# Radio_and_GPS_Rev_A.net
KiCad netlist of a schematic drawn in EAGLE
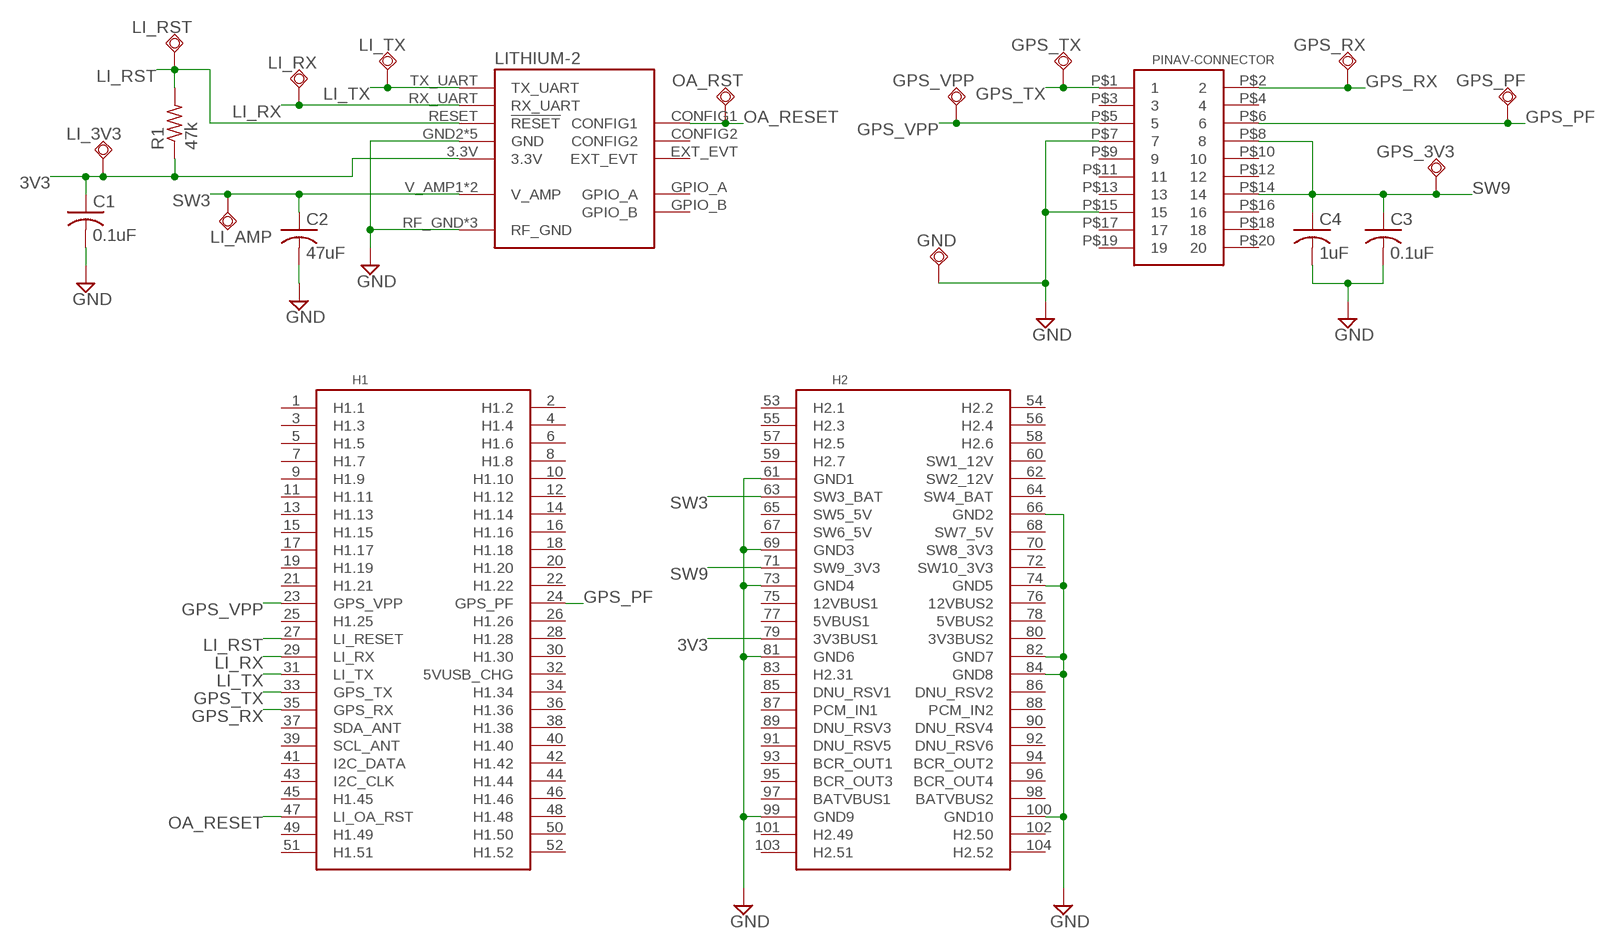
[diagram p0: schematic, sheet 1]

(export (version "E")
  (design (tool "Eeschema 10.0.6"))
  (components
    (comp (ref "C1")
      (value "0.1uF")
      (footprint "eagle-import:C0805")
      (libsource (lib "eagle-import") (part "C-USC0805"))
    )
    (comp (ref "C2")
      (value "47uF")
      (footprint "eagle-import:C0805")
      (libsource (lib "eagle-import") (part "C-USC0805"))
    )
    (comp (ref "C3")
      (value "0.1uF")
      (footprint "eagle-import:C0805")
      (libsource (lib "eagle-import") (part "C-USC0805"))
    )
    (comp (ref "C4")
      (value "1uF")
      (footprint "eagle-import:C0805")
      (libsource (lib "eagle-import") (part "C-USC0805"))
    )
    (comp (ref "GND")
      (value "TPSQTP10SQ")
      (footprint "eagle-import:TP10SQ")
      (libsource (lib "eagle-import") (part "TPSQTP10SQ"))
    )
    (comp (ref "GPS_3V3")
      (value "TPSQTP10SQ")
      (footprint "eagle-import:TP10SQ")
      (libsource (lib "eagle-import") (part "TPSQTP10SQ"))
    )
    (comp (ref "GPS_PF")
      (value "TPSQTP10SQ")
      (footprint "eagle-import:TP10SQ")
      (libsource (lib "eagle-import") (part "TPSQTP10SQ"))
    )
    (comp (ref "GPS_RX")
      (value "TPSQTP10SQ")
      (footprint "eagle-import:TP10SQ")
      (libsource (lib "eagle-import") (part "TPSQTP10SQ"))
    )
    (comp (ref "GPS_TX")
      (value "TPSQTP10SQ")
      (footprint "eagle-import:TP10SQ")
      (libsource (lib "eagle-import") (part "TPSQTP10SQ"))
    )
    (comp (ref "GPS_VPP")
      (value "TPSQTP10SQ")
      (footprint "eagle-import:TP10SQ")
      (libsource (lib "eagle-import") (part "TPSQTP10SQ"))
    )
    (comp (ref "LITHIUM-2")
      (value "LI-2")
      (footprint "eagle-import:LI-2")
      (libsource (lib "eagle-import") (part "LI-2"))
    )
    (comp (ref "LI_3V3")
      (value "TPSQTP10SQ")
      (footprint "eagle-import:TP10SQ")
      (libsource (lib "eagle-import") (part "TPSQTP10SQ"))
    )
    (comp (ref "LI_AMP")
      (value "TPSQTP10SQ")
      (footprint "eagle-import:TP10SQ")
      (libsource (lib "eagle-import") (part "TPSQTP10SQ"))
    )
    (comp (ref "LI_RST")
      (value "TPSQTP10SQ")
      (footprint "eagle-import:TP10SQ")
      (libsource (lib "eagle-import") (part "TPSQTP10SQ"))
    )
    (comp (ref "LI_RX")
      (value "TPSQTP10SQ")
      (footprint "eagle-import:TP10SQ")
      (libsource (lib "eagle-import") (part "TPSQTP10SQ"))
    )
    (comp (ref "LI_TX")
      (value "TPSQTP10SQ")
      (footprint "eagle-import:TP10SQ")
      (libsource (lib "eagle-import") (part "TPSQTP10SQ"))
    )
    (comp (ref "OA_RST")
      (value "TPSQTP10SQ")
      (footprint "eagle-import:TP10SQ")
      (libsource (lib "eagle-import") (part "TPSQTP10SQ"))
    )
    (comp (ref "PINAV-CONNECTOR")
      (value "HLE-110-02-X-DVHLE-110-X-DV-PE-BA")
      (footprint "eagle-import:HLE-110-02-X-DV-PE-BE")
      (libsource (lib "eagle-import") (part "HLE-110-02-X-DVHLE-110-X-DV-PE-BA"))
    )
    (comp (ref "R1")
      (value "47k")
      (footprint "eagle-import:R0805")
      (libsource (lib "eagle-import") (part "R-US_R0805"))
    )
    (comp (ref "U$1")
      (value "PC104_NO_DIMENSION")
      (footprint "eagle-import:PC104_NO_DIMENSION")
      (libsource (lib "eagle-import") (part "PC104_NO_DIMENSION"))
    )
  )
  (nets
    (net (code "1") (name "/3V3") (class "Default")
      (node (ref "C1") (pin "1") (pinfunction "1_1") (pintype "passive"))
      (node (ref "LITHIUM-2") (pin "3.3V") (pinfunction "3.3V_3.3V") (pintype "power_in"))
      (node (ref "LI_3V3") (pin "TP") (pinfunction "TP_TP") (pintype "input"))
      (node (ref "R1") (pin "1") (pinfunction "1_1") (pintype "passive"))
      (node (ref "U$1") (pin "79") (pinfunction "3V3BUS1_79") (pintype "bidirectional"))
    )
    (net (code "2") (name "/GPS_PF") (class "Default")
      (node (ref "GPS_PF") (pin "TP") (pinfunction "TP_TP") (pintype "input"))
      (node (ref "PINAV-CONNECTOR") (pin "P$6") (pinfunction "6_P$6") (pintype "bidirectional"))
      (node (ref "U$1") (pin "24") (pinfunction "GPS_PF_24") (pintype "bidirectional"))
    )
    (net (code "3") (name "/GPS_RX") (class "Default")
      (node (ref "GPS_RX") (pin "TP") (pinfunction "TP_TP") (pintype "input"))
      (node (ref "PINAV-CONNECTOR") (pin "P$2") (pinfunction "2_P$2") (pintype "bidirectional"))
      (node (ref "U$1") (pin "35") (pinfunction "GPS_RX_35") (pintype "bidirectional"))
    )
    (net (code "4") (name "/GPS_TX") (class "Default")
      (node (ref "GPS_TX") (pin "TP") (pinfunction "TP_TP") (pintype "input"))
      (node (ref "PINAV-CONNECTOR") (pin "P$1") (pinfunction "1_P$1") (pintype "bidirectional"))
      (node (ref "U$1") (pin "33") (pinfunction "GPS_TX_33") (pintype "bidirectional"))
    )
    (net (code "5") (name "/GPS_VPP") (class "Default")
      (node (ref "GPS_VPP") (pin "TP") (pinfunction "TP_TP") (pintype "input"))
      (node (ref "PINAV-CONNECTOR") (pin "P$5") (pinfunction "5_P$5") (pintype "bidirectional"))
      (node (ref "U$1") (pin "23") (pinfunction "GPS_VPP_23") (pintype "bidirectional"))
    )
    (net (code "6") (name "/LI_RST") (class "Default")
      (node (ref "LITHIUM-2") (pin "RESET") (pinfunction "~{RESET}_RESET") (pintype "input"))
      (node (ref "LI_RST") (pin "TP") (pinfunction "TP_TP") (pintype "input"))
      (node (ref "R1") (pin "2") (pinfunction "2_2") (pintype "passive"))
      (node (ref "U$1") (pin "27") (pinfunction "LI_RESET_27") (pintype "bidirectional"))
    )
    (net (code "7") (name "/LI_RX") (class "Default")
      (node (ref "LITHIUM-2") (pin "RX_UART") (pinfunction "RX_UART_RX_UART") (pintype "input"))
      (node (ref "LI_RX") (pin "TP") (pinfunction "TP_TP") (pintype "input"))
      (node (ref "U$1") (pin "29") (pinfunction "LI_RX_29") (pintype "bidirectional"))
    )
    (net (code "8") (name "/LI_TX") (class "Default")
      (node (ref "LITHIUM-2") (pin "TX_UART") (pinfunction "TX_UART_TX_UART") (pintype "output"))
      (node (ref "LI_TX") (pin "TP") (pinfunction "TP_TP") (pintype "input"))
      (node (ref "U$1") (pin "31") (pinfunction "LI_TX_31") (pintype "bidirectional"))
    )
    (net (code "9") (name "/OA_RESET") (class "Default")
      (node (ref "LITHIUM-2") (pin "CONFIG1") (pinfunction "CONFIG1_CONFIG1") (pintype "bidirectional"))
      (node (ref "OA_RST") (pin "TP") (pinfunction "TP_TP") (pintype "input"))
      (node (ref "U$1") (pin "47") (pinfunction "LI_OA_RST_47") (pintype "bidirectional"))
    )
    (net (code "10") (name "/SW3") (class "Default")
      (node (ref "C2") (pin "1") (pinfunction "1_1") (pintype "passive"))
      (node (ref "LITHIUM-2") (pin "V_AMP1") (pinfunction "V_AMP_V_AMP1") (pintype "power_in"))
      (node (ref "LITHIUM-2") (pin "V_AMP2") (pinfunction "V_AMP_V_AMP2") (pintype "power_in"))
      (node (ref "LI_AMP") (pin "TP") (pinfunction "TP_TP") (pintype "input"))
      (node (ref "U$1") (pin "63") (pinfunction "SW3_BAT_63") (pintype "bidirectional"))
    )
    (net (code "11") (name "/SW9") (class "Default")
      (node (ref "C3") (pin "1") (pinfunction "1_1") (pintype "passive"))
      (node (ref "C4") (pin "1") (pinfunction "1_1") (pintype "passive"))
      (node (ref "GPS_3V3") (pin "TP") (pinfunction "TP_TP") (pintype "input"))
      (node (ref "PINAV-CONNECTOR") (pin "P$14") (pinfunction "14_P$14") (pintype "bidirectional"))
      (node (ref "PINAV-CONNECTOR") (pin "P$8") (pinfunction "8_P$8") (pintype "bidirectional"))
      (node (ref "U$1") (pin "71") (pinfunction "SW9_3V3_71") (pintype "bidirectional"))
    )
    (net (code "12") (name "GND") (class "Default")
      (node (ref "C1") (pin "2") (pinfunction "2_2") (pintype "passive"))
      (node (ref "C2") (pin "2") (pinfunction "2_2") (pintype "passive"))
      (node (ref "C3") (pin "2") (pinfunction "2_2") (pintype "passive"))
      (node (ref "C4") (pin "2") (pinfunction "2_2") (pintype "passive"))
      (node (ref "GND") (pin "TP") (pinfunction "TP_TP") (pintype "input"))
      (node (ref "LITHIUM-2") (pin "GND2") (pinfunction "GND_GND2") (pintype "power_in"))
      (node (ref "LITHIUM-2") (pin "RF_GND") (pinfunction "RF_GND_RF_GND") (pintype "power_in"))
      (node (ref "LITHIUM-2") (pin "RF_GND1") (pinfunction "RF_GND_RF_GND1") (pintype "power_in"))
      (node (ref "LITHIUM-2") (pin "RF_GND2") (pinfunction "RF_GND_RF_GND2") (pintype "power_in"))
      (node (ref "LITHIUM-2") (pin "THERM1") (pinfunction "GND_THERM1") (pintype "power_in"))
      (node (ref "LITHIUM-2") (pin "THERM2") (pinfunction "GND_THERM2") (pintype "power_in"))
      (node (ref "LITHIUM-2") (pin "THERM3") (pinfunction "GND_THERM3") (pintype "power_in"))
      (node (ref "LITHIUM-2") (pin "THERM4") (pinfunction "GND_THERM4") (pintype "power_in"))
      (node (ref "PINAV-CONNECTOR") (pin "P$15") (pinfunction "15_P$15") (pintype "bidirectional"))
      (node (ref "PINAV-CONNECTOR") (pin "P$7") (pinfunction "7_P$7") (pintype "bidirectional"))
      (node (ref "U$1") (pin "100") (pinfunction "GND10_100") (pintype "bidirectional"))
      (node (ref "U$1") (pin "61") (pinfunction "GND1_61") (pintype "bidirectional"))
      (node (ref "U$1") (pin "66") (pinfunction "GND2_66") (pintype "bidirectional"))
      (node (ref "U$1") (pin "69") (pinfunction "GND3_69") (pintype "bidirectional"))
      (node (ref "U$1") (pin "73") (pinfunction "GND4_73") (pintype "bidirectional"))
      (node (ref "U$1") (pin "74") (pinfunction "GND5_74") (pintype "bidirectional"))
      (node (ref "U$1") (pin "81") (pinfunction "GND6_81") (pintype "bidirectional"))
      (node (ref "U$1") (pin "82") (pinfunction "GND7_82") (pintype "bidirectional"))
      (node (ref "U$1") (pin "84") (pinfunction "GND8_84") (pintype "bidirectional"))
      (node (ref "U$1") (pin "99") (pinfunction "GND9_99") (pintype "bidirectional"))
    )
    (net (code "13") (name "unconnected-(LITHIUM-2-PadCONFIG2)") (class "Default")
      (node (ref "LITHIUM-2") (pin "CONFIG2") (pinfunction "CONFIG2_CONFIG2") (pintype "bidirectional"))
    )
    (net (code "14") (name "unconnected-(LITHIUM-2-PadEXT_EVT)") (class "Default")
      (node (ref "LITHIUM-2") (pin "EXT_EVT") (pinfunction "EXT_EVT_EXT_EVT") (pintype "bidirectional"))
    )
    (net (code "15") (name "unconnected-(LITHIUM-2-PadGPIO_A)") (class "Default")
      (node (ref "LITHIUM-2") (pin "GPIO_A") (pinfunction "GPIO_A_GPIO_A") (pintype "bidirectional"))
    )
    (net (code "16") (name "unconnected-(LITHIUM-2-PadGPIO_B)") (class "Default")
      (node (ref "LITHIUM-2") (pin "GPIO_B") (pinfunction "GPIO_B_GPIO_B") (pintype "bidirectional"))
    )
    (net (code "17") (name "unconnected-(PINAV-CONNECTOR-3-PadP$3)") (class "Default")
      (node (ref "PINAV-CONNECTOR") (pin "P$3") (pinfunction "3_P$3") (pintype "bidirectional"))
    )
    (net (code "18") (name "unconnected-(PINAV-CONNECTOR-4-PadP$4)") (class "Default")
      (node (ref "PINAV-CONNECTOR") (pin "P$4") (pinfunction "4_P$4") (pintype "bidirectional"))
    )
    (net (code "19") (name "unconnected-(PINAV-CONNECTOR-9-PadP$9)") (class "Default")
      (node (ref "PINAV-CONNECTOR") (pin "P$9") (pinfunction "9_P$9") (pintype "bidirectional"))
    )
    (net (code "20") (name "unconnected-(PINAV-CONNECTOR-10-PadP$10)") (class "Default")
      (node (ref "PINAV-CONNECTOR") (pin "P$10") (pinfunction "10_P$10") (pintype "bidirectional"))
    )
    (net (code "21") (name "unconnected-(PINAV-CONNECTOR-11-PadP$11)") (class "Default")
      (node (ref "PINAV-CONNECTOR") (pin "P$11") (pinfunction "11_P$11") (pintype "bidirectional"))
    )
    (net (code "22") (name "unconnected-(PINAV-CONNECTOR-12-PadP$12)") (class "Default")
      (node (ref "PINAV-CONNECTOR") (pin "P$12") (pinfunction "12_P$12") (pintype "bidirectional"))
    )
    (net (code "23") (name "unconnected-(PINAV-CONNECTOR-13-PadP$13)") (class "Default")
      (node (ref "PINAV-CONNECTOR") (pin "P$13") (pinfunction "13_P$13") (pintype "bidirectional"))
    )
    (net (code "24") (name "unconnected-(PINAV-CONNECTOR-16-PadP$16)") (class "Default")
      (node (ref "PINAV-CONNECTOR") (pin "P$16") (pinfunction "16_P$16") (pintype "bidirectional"))
    )
    (net (code "25") (name "unconnected-(PINAV-CONNECTOR-17-PadP$17)") (class "Default")
      (node (ref "PINAV-CONNECTOR") (pin "P$17") (pinfunction "17_P$17") (pintype "bidirectional"))
    )
    (net (code "26") (name "unconnected-(PINAV-CONNECTOR-18-PadP$18)") (class "Default")
      (node (ref "PINAV-CONNECTOR") (pin "P$18") (pinfunction "18_P$18") (pintype "bidirectional"))
    )
    (net (code "27") (name "unconnected-(PINAV-CONNECTOR-19-PadP$19)") (class "Default")
      (node (ref "PINAV-CONNECTOR") (pin "P$19") (pinfunction "19_P$19") (pintype "bidirectional"))
    )
    (net (code "28") (name "unconnected-(PINAV-CONNECTOR-20-PadP$20)") (class "Default")
      (node (ref "PINAV-CONNECTOR") (pin "P$20") (pinfunction "20_P$20") (pintype "bidirectional"))
    )
    (net (code "29") (name "unconnected-(U$1-3V3BUS2-Pad80)") (class "Default")
      (node (ref "U$1") (pin "80") (pinfunction "3V3BUS2_80") (pintype "bidirectional"))
    )
    (net (code "30") (name "unconnected-(U$1-5VBUS1-Pad77)") (class "Default")
      (node (ref "U$1") (pin "77") (pinfunction "5VBUS1_77") (pintype "bidirectional"))
    )
    (net (code "31") (name "unconnected-(U$1-5VBUS2-Pad78)") (class "Default")
      (node (ref "U$1") (pin "78") (pinfunction "5VBUS2_78") (pintype "bidirectional"))
    )
    (net (code "32") (name "unconnected-(U$1-5VUSB_CHG-Pad32)") (class "Default")
      (node (ref "U$1") (pin "32") (pinfunction "5VUSB_CHG_32") (pintype "bidirectional"))
    )
    (net (code "33") (name "unconnected-(U$1-12VBUS1-Pad75)") (class "Default")
      (node (ref "U$1") (pin "75") (pinfunction "12VBUS1_75") (pintype "bidirectional"))
    )
    (net (code "34") (name "unconnected-(U$1-12VBUS2-Pad76)") (class "Default")
      (node (ref "U$1") (pin "76") (pinfunction "12VBUS2_76") (pintype "bidirectional"))
    )
    (net (code "35") (name "unconnected-(U$1-BATVBUS1-Pad97)") (class "Default")
      (node (ref "U$1") (pin "97") (pinfunction "BATVBUS1_97") (pintype "bidirectional"))
    )
    (net (code "36") (name "unconnected-(U$1-BATVBUS2-Pad98)") (class "Default")
      (node (ref "U$1") (pin "98") (pinfunction "BATVBUS2_98") (pintype "bidirectional"))
    )
    (net (code "37") (name "unconnected-(U$1-BCR_OUT1-Pad93)") (class "Default")
      (node (ref "U$1") (pin "93") (pinfunction "BCR_OUT1_93") (pintype "bidirectional"))
    )
    (net (code "38") (name "unconnected-(U$1-BCR_OUT2-Pad94)") (class "Default")
      (node (ref "U$1") (pin "94") (pinfunction "BCR_OUT2_94") (pintype "bidirectional"))
    )
    (net (code "39") (name "unconnected-(U$1-BCR_OUT3-Pad95)") (class "Default")
      (node (ref "U$1") (pin "95") (pinfunction "BCR_OUT3_95") (pintype "bidirectional"))
    )
    (net (code "40") (name "unconnected-(U$1-BCR_OUT4-Pad96)") (class "Default")
      (node (ref "U$1") (pin "96") (pinfunction "BCR_OUT4_96") (pintype "bidirectional"))
    )
    (net (code "41") (name "unconnected-(U$1-DNU_RSV1-Pad85)") (class "Default")
      (node (ref "U$1") (pin "85") (pinfunction "DNU_RSV1_85") (pintype "bidirectional"))
    )
    (net (code "42") (name "unconnected-(U$1-DNU_RSV2-Pad86)") (class "Default")
      (node (ref "U$1") (pin "86") (pinfunction "DNU_RSV2_86") (pintype "bidirectional"))
    )
    (net (code "43") (name "unconnected-(U$1-DNU_RSV3-Pad89)") (class "Default")
      (node (ref "U$1") (pin "89") (pinfunction "DNU_RSV3_89") (pintype "bidirectional"))
    )
    (net (code "44") (name "unconnected-(U$1-DNU_RSV4-Pad90)") (class "Default")
      (node (ref "U$1") (pin "90") (pinfunction "DNU_RSV4_90") (pintype "bidirectional"))
    )
    (net (code "45") (name "unconnected-(U$1-DNU_RSV5-Pad91)") (class "Default")
      (node (ref "U$1") (pin "91") (pinfunction "DNU_RSV5_91") (pintype "bidirectional"))
    )
    (net (code "46") (name "unconnected-(U$1-DNU_RSV6-Pad92)") (class "Default")
      (node (ref "U$1") (pin "92") (pinfunction "DNU_RSV6_92") (pintype "bidirectional"))
    )
    (net (code "47") (name "unconnected-(U$1-H1.1-Pad1)") (class "Default")
      (node (ref "U$1") (pin "1") (pinfunction "H1.1_1") (pintype "bidirectional"))
    )
    (net (code "48") (name "unconnected-(U$1-H1.2-Pad2)") (class "Default")
      (node (ref "U$1") (pin "2") (pinfunction "H1.2_2") (pintype "bidirectional"))
    )
    (net (code "49") (name "unconnected-(U$1-H1.3-Pad3)") (class "Default")
      (node (ref "U$1") (pin "3") (pinfunction "H1.3_3") (pintype "bidirectional"))
    )
    (net (code "50") (name "unconnected-(U$1-H1.4-Pad4)") (class "Default")
      (node (ref "U$1") (pin "4") (pinfunction "H1.4_4") (pintype "bidirectional"))
    )
    (net (code "51") (name "unconnected-(U$1-H1.5-Pad5)") (class "Default")
      (node (ref "U$1") (pin "5") (pinfunction "H1.5_5") (pintype "bidirectional"))
    )
    (net (code "52") (name "unconnected-(U$1-H1.6-Pad6)") (class "Default")
      (node (ref "U$1") (pin "6") (pinfunction "H1.6_6") (pintype "bidirectional"))
    )
    (net (code "53") (name "unconnected-(U$1-H1.7-Pad7)") (class "Default")
      (node (ref "U$1") (pin "7") (pinfunction "H1.7_7") (pintype "bidirectional"))
    )
    (net (code "54") (name "unconnected-(U$1-H1.8-Pad8)") (class "Default")
      (node (ref "U$1") (pin "8") (pinfunction "H1.8_8") (pintype "bidirectional"))
    )
    (net (code "55") (name "unconnected-(U$1-H1.9-Pad9)") (class "Default")
      (node (ref "U$1") (pin "9") (pinfunction "H1.9_9") (pintype "bidirectional"))
    )
    (net (code "56") (name "unconnected-(U$1-H1.10-Pad10)") (class "Default")
      (node (ref "U$1") (pin "10") (pinfunction "H1.10_10") (pintype "bidirectional"))
    )
    (net (code "57") (name "unconnected-(U$1-H1.11-Pad11)") (class "Default")
      (node (ref "U$1") (pin "11") (pinfunction "H1.11_11") (pintype "bidirectional"))
    )
    (net (code "58") (name "unconnected-(U$1-H1.12-Pad12)") (class "Default")
      (node (ref "U$1") (pin "12") (pinfunction "H1.12_12") (pintype "bidirectional"))
    )
    (net (code "59") (name "unconnected-(U$1-H1.13-Pad13)") (class "Default")
      (node (ref "U$1") (pin "13") (pinfunction "H1.13_13") (pintype "bidirectional"))
    )
    (net (code "60") (name "unconnected-(U$1-H1.14-Pad14)") (class "Default")
      (node (ref "U$1") (pin "14") (pinfunction "H1.14_14") (pintype "bidirectional"))
    )
    (net (code "61") (name "unconnected-(U$1-H1.15-Pad15)") (class "Default")
      (node (ref "U$1") (pin "15") (pinfunction "H1.15_15") (pintype "bidirectional"))
    )
    (net (code "62") (name "unconnected-(U$1-H1.16-Pad16)") (class "Default")
      (node (ref "U$1") (pin "16") (pinfunction "H1.16_16") (pintype "bidirectional"))
    )
    (net (code "63") (name "unconnected-(U$1-H1.17-Pad17)") (class "Default")
      (node (ref "U$1") (pin "17") (pinfunction "H1.17_17") (pintype "bidirectional"))
    )
    (net (code "64") (name "unconnected-(U$1-H1.18-Pad18)") (class "Default")
      (node (ref "U$1") (pin "18") (pinfunction "H1.18_18") (pintype "bidirectional"))
    )
    (net (code "65") (name "unconnected-(U$1-H1.19-Pad19)") (class "Default")
      (node (ref "U$1") (pin "19") (pinfunction "H1.19_19") (pintype "bidirectional"))
    )
    (net (code "66") (name "unconnected-(U$1-H1.20-Pad20)") (class "Default")
      (node (ref "U$1") (pin "20") (pinfunction "H1.20_20") (pintype "bidirectional"))
    )
    (net (code "67") (name "unconnected-(U$1-H1.21-Pad21)") (class "Default")
      (node (ref "U$1") (pin "21") (pinfunction "H1.21_21") (pintype "bidirectional"))
    )
    (net (code "68") (name "unconnected-(U$1-H1.22-Pad22)") (class "Default")
      (node (ref "U$1") (pin "22") (pinfunction "H1.22_22") (pintype "bidirectional"))
    )
    (net (code "69") (name "unconnected-(U$1-H1.25-Pad25)") (class "Default")
      (node (ref "U$1") (pin "25") (pinfunction "H1.25_25") (pintype "bidirectional"))
    )
    (net (code "70") (name "unconnected-(U$1-H1.26-Pad26)") (class "Default")
      (node (ref "U$1") (pin "26") (pinfunction "H1.26_26") (pintype "bidirectional"))
    )
    (net (code "71") (name "unconnected-(U$1-H1.28-Pad28)") (class "Default")
      (node (ref "U$1") (pin "28") (pinfunction "H1.28_28") (pintype "bidirectional"))
    )
    (net (code "72") (name "unconnected-(U$1-H1.30-Pad30)") (class "Default")
      (node (ref "U$1") (pin "30") (pinfunction "H1.30_30") (pintype "bidirectional"))
    )
    (net (code "73") (name "unconnected-(U$1-H1.34-Pad34)") (class "Default")
      (node (ref "U$1") (pin "34") (pinfunction "H1.34_34") (pintype "bidirectional"))
    )
    (net (code "74") (name "unconnected-(U$1-H1.36-Pad36)") (class "Default")
      (node (ref "U$1") (pin "36") (pinfunction "H1.36_36") (pintype "bidirectional"))
    )
    (net (code "75") (name "unconnected-(U$1-H1.38-Pad38)") (class "Default")
      (node (ref "U$1") (pin "38") (pinfunction "H1.38_38") (pintype "bidirectional"))
    )
    (net (code "76") (name "unconnected-(U$1-H1.40-Pad40)") (class "Default")
      (node (ref "U$1") (pin "40") (pinfunction "H1.40_40") (pintype "bidirectional"))
    )
    (net (code "77") (name "unconnected-(U$1-H1.42-Pad42)") (class "Default")
      (node (ref "U$1") (pin "42") (pinfunction "H1.42_42") (pintype "bidirectional"))
    )
    (net (code "78") (name "unconnected-(U$1-H1.44-Pad44)") (class "Default")
      (node (ref "U$1") (pin "44") (pinfunction "H1.44_44") (pintype "bidirectional"))
    )
    (net (code "79") (name "unconnected-(U$1-H1.45-Pad45)") (class "Default")
      (node (ref "U$1") (pin "45") (pinfunction "H1.45_45") (pintype "bidirectional"))
    )
    (net (code "80") (name "unconnected-(U$1-H1.46-Pad46)") (class "Default")
      (node (ref "U$1") (pin "46") (pinfunction "H1.46_46") (pintype "bidirectional"))
    )
    (net (code "81") (name "unconnected-(U$1-H1.48-Pad48)") (class "Default")
      (node (ref "U$1") (pin "48") (pinfunction "H1.48_48") (pintype "bidirectional"))
    )
    (net (code "82") (name "unconnected-(U$1-H1.49-Pad49)") (class "Default")
      (node (ref "U$1") (pin "49") (pinfunction "H1.49_49") (pintype "bidirectional"))
    )
    (net (code "83") (name "unconnected-(U$1-H1.50-Pad50)") (class "Default")
      (node (ref "U$1") (pin "50") (pinfunction "H1.50_50") (pintype "bidirectional"))
    )
    (net (code "84") (name "unconnected-(U$1-H1.51-Pad51)") (class "Default")
      (node (ref "U$1") (pin "51") (pinfunction "H1.51_51") (pintype "bidirectional"))
    )
    (net (code "85") (name "unconnected-(U$1-H1.52-Pad52)") (class "Default")
      (node (ref "U$1") (pin "52") (pinfunction "H1.52_52") (pintype "bidirectional"))
    )
    (net (code "86") (name "unconnected-(U$1-H2.1-Pad53)") (class "Default")
      (node (ref "U$1") (pin "53") (pinfunction "H2.1_53") (pintype "bidirectional"))
    )
    (net (code "87") (name "unconnected-(U$1-H2.2-Pad54)") (class "Default")
      (node (ref "U$1") (pin "54") (pinfunction "H2.2_54") (pintype "bidirectional"))
    )
    (net (code "88") (name "unconnected-(U$1-H2.3-Pad55)") (class "Default")
      (node (ref "U$1") (pin "55") (pinfunction "H2.3_55") (pintype "bidirectional"))
    )
    (net (code "89") (name "unconnected-(U$1-H2.4-Pad56)") (class "Default")
      (node (ref "U$1") (pin "56") (pinfunction "H2.4_56") (pintype "bidirectional"))
    )
    (net (code "90") (name "unconnected-(U$1-H2.5-Pad57)") (class "Default")
      (node (ref "U$1") (pin "57") (pinfunction "H2.5_57") (pintype "bidirectional"))
    )
    (net (code "91") (name "unconnected-(U$1-H2.6-Pad58)") (class "Default")
      (node (ref "U$1") (pin "58") (pinfunction "H2.6_58") (pintype "bidirectional"))
    )
    (net (code "92") (name "unconnected-(U$1-H2.7-Pad59)") (class "Default")
      (node (ref "U$1") (pin "59") (pinfunction "H2.7_59") (pintype "bidirectional"))
    )
    (net (code "93") (name "unconnected-(U$1-H2.31-Pad83)") (class "Default")
      (node (ref "U$1") (pin "83") (pinfunction "H2.31_83") (pintype "bidirectional"))
    )
    (net (code "94") (name "unconnected-(U$1-H2.49-Pad101)") (class "Default")
      (node (ref "U$1") (pin "101") (pinfunction "H2.49_101") (pintype "bidirectional"))
    )
    (net (code "95") (name "unconnected-(U$1-H2.50-Pad102)") (class "Default")
      (node (ref "U$1") (pin "102") (pinfunction "H2.50_102") (pintype "bidirectional"))
    )
    (net (code "96") (name "unconnected-(U$1-H2.51-Pad103)") (class "Default")
      (node (ref "U$1") (pin "103") (pinfunction "H2.51_103") (pintype "bidirectional"))
    )
    (net (code "97") (name "unconnected-(U$1-H2.52-Pad104)") (class "Default")
      (node (ref "U$1") (pin "104") (pinfunction "H2.52_104") (pintype "bidirectional"))
    )
    (net (code "98") (name "unconnected-(U$1-I2C_CLK-Pad43)") (class "Default")
      (node (ref "U$1") (pin "43") (pinfunction "I2C_CLK_43") (pintype "bidirectional"))
    )
    (net (code "99") (name "unconnected-(U$1-I2C_DATA-Pad41)") (class "Default")
      (node (ref "U$1") (pin "41") (pinfunction "I2C_DATA_41") (pintype "bidirectional"))
    )
    (net (code "100") (name "unconnected-(U$1-PCM_IN1-Pad87)") (class "Default")
      (node (ref "U$1") (pin "87") (pinfunction "PCM_IN1_87") (pintype "bidirectional"))
    )
    (net (code "101") (name "unconnected-(U$1-PCM_IN2-Pad88)") (class "Default")
      (node (ref "U$1") (pin "88") (pinfunction "PCM_IN2_88") (pintype "bidirectional"))
    )
    (net (code "102") (name "unconnected-(U$1-SCL_ANT-Pad39)") (class "Default")
      (node (ref "U$1") (pin "39") (pinfunction "SCL_ANT_39") (pintype "bidirectional"))
    )
    (net (code "103") (name "unconnected-(U$1-SDA_ANT-Pad37)") (class "Default")
      (node (ref "U$1") (pin "37") (pinfunction "SDA_ANT_37") (pintype "bidirectional"))
    )
    (net (code "104") (name "unconnected-(U$1-SW1_12V-Pad60)") (class "Default")
      (node (ref "U$1") (pin "60") (pinfunction "SW1_12V_60") (pintype "bidirectional"))
    )
    (net (code "105") (name "unconnected-(U$1-SW2_12V-Pad62)") (class "Default")
      (node (ref "U$1") (pin "62") (pinfunction "SW2_12V_62") (pintype "bidirectional"))
    )
    (net (code "106") (name "unconnected-(U$1-SW4_BAT-Pad64)") (class "Default")
      (node (ref "U$1") (pin "64") (pinfunction "SW4_BAT_64") (pintype "bidirectional"))
    )
    (net (code "107") (name "unconnected-(U$1-SW5_5V-Pad65)") (class "Default")
      (node (ref "U$1") (pin "65") (pinfunction "SW5_5V_65") (pintype "bidirectional"))
    )
    (net (code "108") (name "unconnected-(U$1-SW6_5V-Pad67)") (class "Default")
      (node (ref "U$1") (pin "67") (pinfunction "SW6_5V_67") (pintype "bidirectional"))
    )
    (net (code "109") (name "unconnected-(U$1-SW7_5V-Pad68)") (class "Default")
      (node (ref "U$1") (pin "68") (pinfunction "SW7_5V_68") (pintype "bidirectional"))
    )
    (net (code "110") (name "unconnected-(U$1-SW8_3V3-Pad70)") (class "Default")
      (node (ref "U$1") (pin "70") (pinfunction "SW8_3V3_70") (pintype "bidirectional"))
    )
    (net (code "111") (name "unconnected-(U$1-SW10_3V3-Pad72)") (class "Default")
      (node (ref "U$1") (pin "72") (pinfunction "SW10_3V3_72") (pintype "bidirectional"))
    )
  )
)
